# SpeccyPower5v.net
KiCad netlist of a schematic drawn in EAGLE
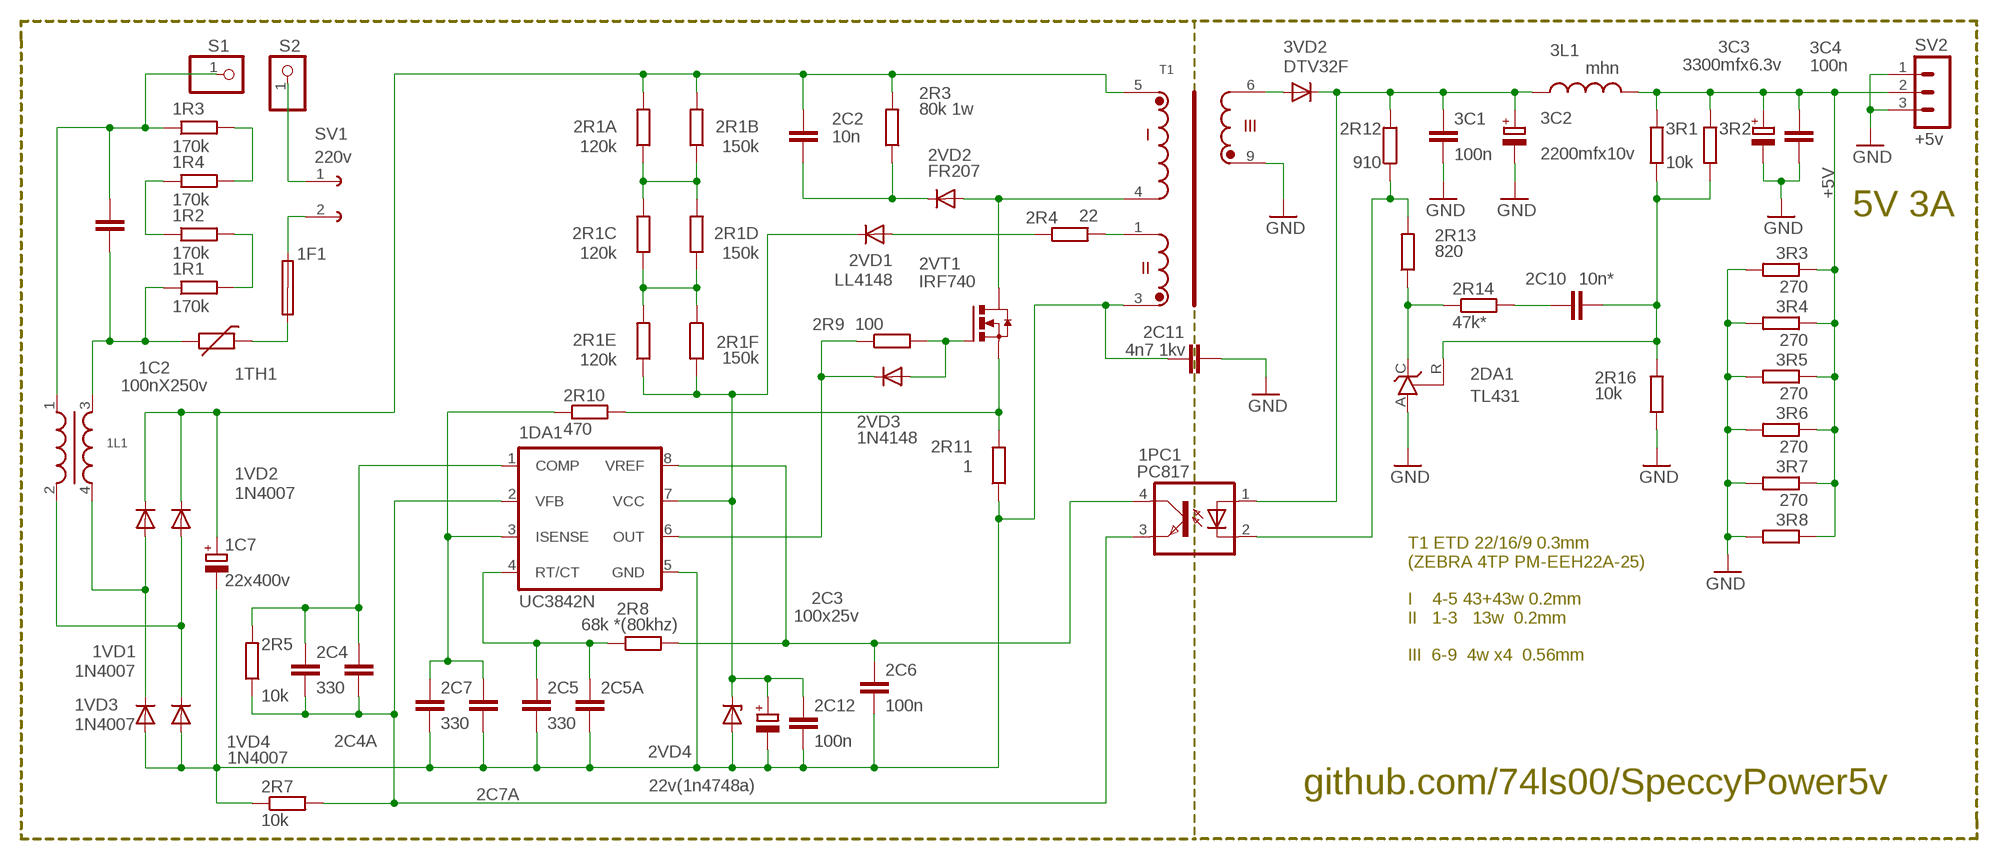
[diagram p0: schematic, sheet 1]

(export (version "E")
  (design (tool "Eeschema 10.0.6"))
  (components
    (comp (ref "1C2")
      (value "100nX250v")
      (footprint "eagle-import:C150-064X183")
      (libsource (lib "eagle-import") (part "C-EU150-064X183"))
    )
    (comp (ref "1C7")
      (value "22x400v")
      (footprint "eagle-import:TT5D11L")
      (libsource (lib "eagle-import") (part "CPOL-EUTT5D11L"))
    )
    (comp (ref "1DA1")
      (value "UC3842N")
      (footprint "eagle-import:DIL08")
      (libsource (lib "eagle-import") (part "UC384N2"))
    )
    (comp (ref "1F1")
      (value "SHK20L")
      (footprint "eagle-import:SHK20L")
      (libsource (lib "eagle-import") (part "SHK20L"))
    )
    (comp (ref "1L1")
      (value "LFLF-10X13")
      (footprint "eagle-import:LF-10X13")
      (libsource (lib "eagle-import") (part "LFLF-10X13"))
    )
    (comp (ref "1PC1")
      (value "PC817")
      (footprint "eagle-import:DIL04")
      (fields (field (name "MPN") "PC817X4J000F"))
      (libsource (lib "eagle-import") (part "PC817"))
    )
    (comp (ref "1R1")
      (value "170k")
      (footprint "eagle-import:R0805")
      (libsource (lib "eagle-import") (part "R-EU_R0805"))
    )
    (comp (ref "1R2")
      (value "170k")
      (footprint "eagle-import:R0805")
      (libsource (lib "eagle-import") (part "R-EU_R0805"))
    )
    (comp (ref "1R3")
      (value "170k")
      (footprint "eagle-import:R0805")
      (libsource (lib "eagle-import") (part "R-EU_R0805"))
    )
    (comp (ref "1R4")
      (value "170k")
      (footprint "eagle-import:R0805")
      (libsource (lib "eagle-import") (part "R-EU_R0805"))
    )
    (comp (ref "1TH1")
      (value "THERMISTOR-7,5")
      (footprint "eagle-import:R-7,5")
      (libsource (lib "eagle-import") (part "THERMISTOR-7,5"))
    )
    (comp (ref "1VD1")
      (value "1N4007")
      (footprint "eagle-import:DO41-10")
      (libsource (lib "eagle-import") (part "1N4004"))
    )
    (comp (ref "1VD2")
      (value "1N4007")
      (footprint "eagle-import:DO41-10")
      (libsource (lib "eagle-import") (part "1N4004"))
    )
    (comp (ref "1VD3")
      (value "1N4007")
      (footprint "eagle-import:DO41-10")
      (libsource (lib "eagle-import") (part "1N4004"))
    )
    (comp (ref "1VD4")
      (value "1N4007")
      (footprint "eagle-import:DO41-10")
      (libsource (lib "eagle-import") (part "1N4004"))
    )
    (comp (ref "2C2")
      (value "10n")
      (footprint "eagle-import:C102-043X133")
      (libsource (lib "eagle-import") (part "rcl_C-EU102-043X133"))
    )
    (comp (ref "2C3")
      (value "100x25v")
      (footprint "eagle-import:E2,5-6")
      (libsource (lib "eagle-import") (part "rcl_CPOL-EUE2.5-6"))
    )
    (comp (ref "2C4")
      (value "330")
      (footprint "eagle-import:C050-025X075")
      (libsource (lib "eagle-import") (part "rcl_C-EU050-025X075"))
    )
    (comp (ref "2C4A")
      (value "C-EUC0805")
      (footprint "eagle-import:C0805")
      (libsource (lib "eagle-import") (part "rcl_C-EUC0805"))
    )
    (comp (ref "2C5")
      (value "330")
      (footprint "eagle-import:C050-025X075")
      (libsource (lib "eagle-import") (part "rcl_C-EU050-025X075"))
    )
    (comp (ref "2C5A")
      (value "C-EUC0805")
      (footprint "eagle-import:C0805")
      (libsource (lib "eagle-import") (part "rcl_C-EUC0805"))
    )
    (comp (ref "2C6")
      (value "100n")
      (footprint "eagle-import:C0805")
      (libsource (lib "eagle-import") (part "rcl_C-EUC0805"))
    )
    (comp (ref "2C7")
      (value "330")
      (footprint "eagle-import:C050-025X075")
      (libsource (lib "eagle-import") (part "rcl_C-EU050-025X075"))
    )
    (comp (ref "2C7A")
      (value "C-EUC0805")
      (footprint "eagle-import:C0805")
      (libsource (lib "eagle-import") (part "rcl_C-EUC0805"))
    )
    (comp (ref "2C10")
      (value "10n*")
      (footprint "eagle-import:C050-025X075")
      (libsource (lib "eagle-import") (part "rcl_C-EU050-025X075"))
    )
    (comp (ref "2C11")
      (value "4n7 1kv")
      (footprint "eagle-import:C075-032X103")
      (libsource (lib "eagle-import") (part "rcl_C-EU075-032X103"))
    )
    (comp (ref "2C12")
      (value "100n")
      (footprint "eagle-import:C0805")
      (libsource (lib "eagle-import") (part "rcl_C-EUC0805"))
    )
    (comp (ref "2DA1")
      (value "TL431")
      (footprint "eagle-import:TO92-CLP")
      (libsource (lib "eagle-import") (part "TL431CLP"))
    )
    (comp (ref "2R1A")
      (value "120k")
      (footprint "eagle-import:M0805")
      (libsource (lib "eagle-import") (part "R-EU_M0805"))
    )
    (comp (ref "2R1B")
      (value "150k")
      (footprint "eagle-import:M0805")
      (libsource (lib "eagle-import") (part "R-EU_M0805"))
    )
    (comp (ref "2R1C")
      (value "120k")
      (footprint "eagle-import:M0805")
      (libsource (lib "eagle-import") (part "R-EU_M0805"))
    )
    (comp (ref "2R1D")
      (value "150k")
      (footprint "eagle-import:M0805")
      (libsource (lib "eagle-import") (part "R-EU_M0805"))
    )
    (comp (ref "2R1E")
      (value "120k")
      (footprint "eagle-import:M0805")
      (libsource (lib "eagle-import") (part "R-EU_M0805"))
    )
    (comp (ref "2R1F")
      (value "150k")
      (footprint "eagle-import:M0805")
      (libsource (lib "eagle-import") (part "R-EU_M0805"))
    )
    (comp (ref "2R3")
      (value "80k 1w")
      (footprint "eagle-import:P0613_15")
      (libsource (lib "eagle-import") (part "R-EU_0613/15"))
    )
    (comp (ref "2R4")
      (value "22")
      (footprint "eagle-import:M0805")
      (libsource (lib "eagle-import") (part "R-EU_M0805"))
    )
    (comp (ref "2R5")
      (value "10k")
      (footprint "eagle-import:0207_10")
      (libsource (lib "eagle-import") (part "R-EU_0207/10"))
    )
    (comp (ref "2R7")
      (value "10k")
      (footprint "eagle-import:0207_10")
      (libsource (lib "eagle-import") (part "R-EU_0207/10"))
    )
    (comp (ref "2R8")
      (value "68k *(80khz)")
      (footprint "eagle-import:R0805")
      (libsource (lib "eagle-import") (part "R-EU_R0805"))
    )
    (comp (ref "2R9")
      (value "100")
      (footprint "eagle-import:0204_7")
      (libsource (lib "eagle-import") (part "R-EU_0204/7"))
    )
    (comp (ref "2R10")
      (value "470")
      (footprint "eagle-import:0207_10")
      (libsource (lib "eagle-import") (part "R-EU_0207/10"))
    )
    (comp (ref "2R11")
      (value "1")
      (footprint "eagle-import:0411_15")
      (libsource (lib "eagle-import") (part "R-EU_0411/15"))
    )
    (comp (ref "2R12")
      (value "910")
      (footprint "eagle-import:R0805")
      (libsource (lib "eagle-import") (part "R-EU_R0805"))
    )
    (comp (ref "2R13")
      (value "820")
      (footprint "eagle-import:0204_7")
      (libsource (lib "eagle-import") (part "R-EU_0204/7"))
    )
    (comp (ref "2R14")
      (value "47k*")
      (footprint "eagle-import:R0805")
      (libsource (lib "eagle-import") (part "R-EU_R0805"))
    )
    (comp (ref "2R16")
      (value "10k")
      (footprint "eagle-import:R0805")
      (libsource (lib "eagle-import") (part "R-EU_R0805"))
    )
    (comp (ref "2VD1")
      (value "LL4148")
      (footprint "eagle-import:SOD80C")
      (libsource (lib "eagle-import") (part "DIODE-SOD80C"))
    )
    (comp (ref "2VD2")
      (value "FR207")
      (footprint "eagle-import:DO35-10")
      (libsource (lib "eagle-import") (part "1N4148DO35-10"))
    )
    (comp (ref "2VD3")
      (value "1N4148")
      (footprint "eagle-import:DO35-7")
      (libsource (lib "eagle-import") (part "1N4148DO35-7"))
    )
    (comp (ref "2VD4")
      (value "22v(1n4748a)")
      (footprint "eagle-import:DO35Z10")
      (libsource (lib "eagle-import") (part "ZENER-DIODEDO35Z10"))
    )
    (comp (ref "2VT1")
      (value "IRF740")
      (footprint "eagle-import:TO262-V")
      (libsource (lib "eagle-import") (part "IRF3704L-V"))
    )
    (comp (ref "3C1")
      (value "100n")
      (footprint "eagle-import:C0805")
      (libsource (lib "eagle-import") (part "rcl_C-EUC0805"))
    )
    (comp (ref "3C2")
      (value "2200mfx10v")
      (footprint "eagle-import:TT2D7L")
      (libsource (lib "eagle-import") (part "CPOL-EUTT2D7L"))
    )
    (comp (ref "3C3")
      (value "3300mfx6.3v")
      (footprint "eagle-import:TT2D7L-2")
      (libsource (lib "eagle-import") (part "CPOL-EUTT2D7L-2"))
    )
    (comp (ref "3C4")
      (value "100n")
      (footprint "eagle-import:C0805")
      (libsource (lib "eagle-import") (part "rcl_C-EUC0805"))
    )
    (comp (ref "3L1")
      (value "mhn")
      (footprint "eagle-import:LAL02")
      (libsource (lib "eagle-import") (part "L-USLAL02"))
    )
    (comp (ref "3R1")
      (value "10k")
      (footprint "eagle-import:R0805")
      (libsource (lib "eagle-import") (part "R-EU_R0805"))
    )
    (comp (ref "3R2")
      (value "R-EU_R0805")
      (footprint "eagle-import:R0805")
      (libsource (lib "eagle-import") (part "R-EU_R0805"))
    )
    (comp (ref "3R3")
      (value "270")
      (footprint "eagle-import:R0805")
      (libsource (lib "eagle-import") (part "R-EU_R0805"))
    )
    (comp (ref "3R4")
      (value "270")
      (footprint "eagle-import:R0805")
      (libsource (lib "eagle-import") (part "R-EU_R0805"))
    )
    (comp (ref "3R5")
      (value "270")
      (footprint "eagle-import:R0805")
      (libsource (lib "eagle-import") (part "R-EU_R0805"))
    )
    (comp (ref "3R6")
      (value "270")
      (footprint "eagle-import:R0805")
      (libsource (lib "eagle-import") (part "R-EU_R0805"))
    )
    (comp (ref "3R7")
      (value "270")
      (footprint "eagle-import:R0805")
      (libsource (lib "eagle-import") (part "R-EU_R0805"))
    )
    (comp (ref "3R8")
      (value "R-EU_R0805")
      (footprint "eagle-import:R0805")
      (libsource (lib "eagle-import") (part "R-EU_R0805"))
    )
    (comp (ref "3VD2")
      (value "DTV32F")
      (footprint "eagle-import:DO220S")
      (libsource (lib "eagle-import") (part "DIODE-DO220S"))
    )
    (comp (ref "S1")
      (value "PINHD-1X1")
      (footprint "eagle-import:1X01")
      (libsource (lib "eagle-import") (part "PINHD-1X1"))
    )
    (comp (ref "S2")
      (value "PINHD-1X1")
      (footprint "eagle-import:1X01")
      (libsource (lib "eagle-import") (part "PINHD-1X1"))
    )
    (comp (ref "SV1")
      (value "220v")
      (footprint "eagle-import:IEC320-C8")
      (libsource (lib "eagle-import") (part "IEC320-C8"))
    )
    (comp (ref "SV2")
      (value "+5v")
      (footprint "eagle-import:MA03-1")
      (libsource (lib "eagle-import") (part "MA03-1"))
    )
    (comp (ref "T1")
      (value "TRANS_ER29")
      (footprint "eagle-import:ER29")
      (libsource (lib "eagle-import") (part "TRANS_ER29"))
    )
  )
  (nets
    (net (code "1") (name "/+5V") (class "Default")
      (node (ref "3C3") (pin "+") (pinfunction "+_+") (pintype "passive"))
      (node (ref "3C4") (pin "1") (pinfunction "1_1") (pintype "passive"))
      (node (ref "3L1") (pin "2") (pinfunction "2_2") (pintype "passive"))
      (node (ref "3R1") (pin "2") (pinfunction "2_2") (pintype "passive"))
      (node (ref "3R2") (pin "2") (pinfunction "2_2") (pintype "passive"))
      (node (ref "3R3") (pin "1") (pinfunction "1_1") (pintype "passive"))
      (node (ref "3R4") (pin "1") (pinfunction "1_1") (pintype "passive"))
      (node (ref "3R5") (pin "1") (pinfunction "1_1") (pintype "passive"))
      (node (ref "3R6") (pin "1") (pinfunction "1_1") (pintype "passive"))
      (node (ref "3R7") (pin "1") (pinfunction "1_1") (pintype "passive"))
      (node (ref "3R8") (pin "1") (pinfunction "1_1") (pintype "passive"))
      (node (ref "SV2") (pin "2") (pinfunction "2_2") (pintype "passive"))
    )
    (net (code "2") (name "GND") (class "Default")
      (node (ref "2C11") (pin "2") (pinfunction "2_2") (pintype "passive"))
      (node (ref "2DA1") (pin "A") (pinfunction "A_A") (pintype "passive"))
      (node (ref "2R16") (pin "1") (pinfunction "1_1") (pintype "passive"))
      (node (ref "3C1") (pin "2") (pinfunction "2_2") (pintype "passive"))
      (node (ref "3C2") (pin "-") (pinfunction "-_-") (pintype "passive"))
      (node (ref "3C3") (pin "-") (pinfunction "-_-") (pintype "passive"))
      (node (ref "3C4") (pin "2") (pinfunction "2_2") (pintype "passive"))
      (node (ref "3R3") (pin "2") (pinfunction "2_2") (pintype "passive"))
      (node (ref "3R4") (pin "2") (pinfunction "2_2") (pintype "passive"))
      (node (ref "3R5") (pin "2") (pinfunction "2_2") (pintype "passive"))
      (node (ref "3R6") (pin "2") (pinfunction "2_2") (pintype "passive"))
      (node (ref "3R7") (pin "2") (pinfunction "2_2") (pintype "passive"))
      (node (ref "3R8") (pin "2") (pinfunction "2_2") (pintype "passive"))
      (node (ref "SV2") (pin "1") (pinfunction "1_1") (pintype "passive"))
      (node (ref "SV2") (pin "3") (pinfunction "3_3") (pintype "passive"))
      (node (ref "T1") (pin "9") (pinfunction "5V2_9") (pintype "bidirectional"))
    )
    (net (code "3") (name "Net-(1C2-Pad1)") (class "Default")
      (node (ref "1C2") (pin "1") (pinfunction "1_1") (pintype "passive"))
      (node (ref "1L1") (pin "3") (pinfunction "3_3") (pintype "bidirectional"))
      (node (ref "1R1") (pin "1") (pinfunction "1_1") (pintype "passive"))
      (node (ref "1TH1") (pin "2") (pinfunction "2_2") (pintype "passive"))
    )
    (net (code "4") (name "Net-(1C2-Pad2)") (class "Default")
      (node (ref "1C2") (pin "2") (pinfunction "2_2") (pintype "passive"))
      (node (ref "1L1") (pin "1") (pinfunction "1_1") (pintype "bidirectional"))
      (node (ref "1R3") (pin "1") (pinfunction "1_1") (pintype "passive"))
      (node (ref "S1") (pin "1") (pinfunction "1_1") (pintype "passive"))
    )
    (net (code "5") (name "Net-(1DA1-COMP)") (class "Default")
      (node (ref "1DA1") (pin "1") (pinfunction "COMP_1") (pintype "passive"))
      (node (ref "2C4") (pin "1") (pinfunction "1_1") (pintype "passive"))
      (node (ref "2C4A") (pin "1") (pinfunction "1_1") (pintype "passive"))
      (node (ref "2R5") (pin "2") (pinfunction "2_2") (pintype "passive"))
    )
    (net (code "6") (name "Net-(1DA1-GND)") (class "Default")
      (node (ref "1C7") (pin "-") (pinfunction "-_-") (pintype "passive"))
      (node (ref "1DA1") (pin "5") (pinfunction "GND_5") (pintype "power_in"))
      (node (ref "1VD3") (pin "A") (pinfunction "A_A") (pintype "passive"))
      (node (ref "1VD4") (pin "A") (pinfunction "A_A") (pintype "passive"))
      (node (ref "2C11") (pin "1") (pinfunction "1_1") (pintype "passive"))
      (node (ref "2C12") (pin "2") (pinfunction "2_2") (pintype "passive"))
      (node (ref "2C3") (pin "-") (pinfunction "-_-") (pintype "passive"))
      (node (ref "2C5") (pin "2") (pinfunction "2_2") (pintype "passive"))
      (node (ref "2C5A") (pin "2") (pinfunction "2_2") (pintype "passive"))
      (node (ref "2C6") (pin "2") (pinfunction "2_2") (pintype "passive"))
      (node (ref "2C7") (pin "2") (pinfunction "2_2") (pintype "passive"))
      (node (ref "2C7A") (pin "2") (pinfunction "2_2") (pintype "passive"))
      (node (ref "2R11") (pin "1") (pinfunction "1_1") (pintype "passive"))
      (node (ref "2R7") (pin "1") (pinfunction "1_1") (pintype "passive"))
      (node (ref "2VD4") (pin "A") (pinfunction "A_A") (pintype "passive"))
      (node (ref "T1") (pin "3") (pinfunction "OP2_3") (pintype "bidirectional"))
    )
    (net (code "7") (name "Net-(1DA1-ISENSE)") (class "Default")
      (node (ref "1DA1") (pin "3") (pinfunction "ISENSE_3") (pintype "input"))
      (node (ref "2C7") (pin "1") (pinfunction "1_1") (pintype "passive"))
      (node (ref "2C7A") (pin "1") (pinfunction "1_1") (pintype "passive"))
      (node (ref "2R10") (pin "1") (pinfunction "1_1") (pintype "passive"))
    )
    (net (code "8") (name "Net-(1DA1-OUT)") (class "Default")
      (node (ref "1DA1") (pin "6") (pinfunction "OUT_6") (pintype "output"))
      (node (ref "2R9") (pin "1") (pinfunction "1_1") (pintype "passive"))
      (node (ref "2VD3") (pin "C") (pinfunction "C_C") (pintype "passive"))
    )
    (net (code "9") (name "Net-(1DA1-RT{slash}CT)") (class "Default")
      (node (ref "1DA1") (pin "4") (pinfunction "RT/CT_4") (pintype "passive"))
      (node (ref "2C5") (pin "1") (pinfunction "1_1") (pintype "passive"))
      (node (ref "2C5A") (pin "1") (pinfunction "1_1") (pintype "passive"))
      (node (ref "2R8") (pin "1") (pinfunction "1_1") (pintype "passive"))
    )
    (net (code "10") (name "Net-(1DA1-VCC)") (class "Default")
      (node (ref "1DA1") (pin "7") (pinfunction "VCC_7") (pintype "power_in"))
      (node (ref "2C12") (pin "1") (pinfunction "1_1") (pintype "passive"))
      (node (ref "2C3") (pin "+") (pinfunction "+_+") (pintype "passive"))
      (node (ref "2R1E") (pin "1") (pinfunction "1_1") (pintype "passive"))
      (node (ref "2R1F") (pin "2") (pinfunction "2_2") (pintype "passive"))
      (node (ref "2VD1") (pin "C") (pinfunction "C_C") (pintype "passive"))
      (node (ref "2VD4") (pin "C") (pinfunction "C_C") (pintype "passive"))
    )
    (net (code "11") (name "Net-(1DA1-VFB)") (class "Default")
      (node (ref "1DA1") (pin "2") (pinfunction "VFB_2") (pintype "input"))
      (node (ref "1PC1") (pin "3") (pinfunction "EMIT_3") (pintype "passive"))
      (node (ref "2C4") (pin "2") (pinfunction "2_2") (pintype "passive"))
      (node (ref "2C4A") (pin "2") (pinfunction "2_2") (pintype "passive"))
      (node (ref "2R5") (pin "1") (pinfunction "1_1") (pintype "passive"))
      (node (ref "2R7") (pin "2") (pinfunction "2_2") (pintype "passive"))
    )
    (net (code "12") (name "Net-(1DA1-VREF)") (class "Default")
      (node (ref "1DA1") (pin "8") (pinfunction "VREF_8") (pintype "passive"))
      (node (ref "1PC1") (pin "4") (pinfunction "COL_4") (pintype "passive"))
      (node (ref "2C6") (pin "1") (pinfunction "1_1") (pintype "passive"))
      (node (ref "2R8") (pin "2") (pinfunction "2_2") (pintype "passive"))
    )
    (net (code "13") (name "Net-(1F1-Pad1A)") (class "Default")
      (node (ref "1F1") (pin "1A") (pinfunction "1A_1A") (pintype "passive"))
      (node (ref "SV1") (pin "2") (pinfunction "2_2") (pintype "passive"))
    )
    (net (code "14") (name "Net-(1F1-Pad2A)") (class "Default")
      (node (ref "1F1") (pin "2A") (pinfunction "2A_2A") (pintype "passive"))
      (node (ref "1TH1") (pin "1") (pinfunction "1_1") (pintype "passive"))
    )
    (net (code "15") (name "Net-(1L1-Pad2)") (class "Default")
      (node (ref "1L1") (pin "2") (pinfunction "2_2") (pintype "bidirectional"))
      (node (ref "1VD2") (pin "A") (pinfunction "A_A") (pintype "passive"))
      (node (ref "1VD4") (pin "C") (pinfunction "C_C") (pintype "passive"))
    )
    (net (code "16") (name "Net-(1L1-Pad4)") (class "Default")
      (node (ref "1L1") (pin "4") (pinfunction "4_4") (pintype "bidirectional"))
      (node (ref "1VD1") (pin "A") (pinfunction "A_A") (pintype "passive"))
      (node (ref "1VD3") (pin "C") (pinfunction "C_C") (pintype "passive"))
    )
    (net (code "17") (name "Net-(1PC1-A)") (class "Default")
      (node (ref "1PC1") (pin "1") (pinfunction "A_1") (pintype "passive"))
      (node (ref "2R12") (pin "2") (pinfunction "2_2") (pintype "passive"))
      (node (ref "3C1") (pin "1") (pinfunction "1_1") (pintype "passive"))
      (node (ref "3C2") (pin "+") (pinfunction "+_+") (pintype "passive"))
      (node (ref "3L1") (pin "1") (pinfunction "1_1") (pintype "passive"))
      (node (ref "3VD2") (pin "C") (pinfunction "C_C") (pintype "passive"))
    )
    (net (code "18") (name "Net-(1PC1-C)") (class "Default")
      (node (ref "1PC1") (pin "2") (pinfunction "C_2") (pintype "passive"))
      (node (ref "2R12") (pin "1") (pinfunction "1_1") (pintype "passive"))
      (node (ref "2R13") (pin "2") (pinfunction "2_2") (pintype "passive"))
    )
    (net (code "19") (name "Net-(1R1-Pad2)") (class "Default")
      (node (ref "1R1") (pin "2") (pinfunction "2_2") (pintype "passive"))
      (node (ref "1R2") (pin "2") (pinfunction "2_2") (pintype "passive"))
    )
    (net (code "20") (name "Net-(1R2-Pad1)") (class "Default")
      (node (ref "1R2") (pin "1") (pinfunction "1_1") (pintype "passive"))
      (node (ref "1R4") (pin "1") (pinfunction "1_1") (pintype "passive"))
    )
    (net (code "21") (name "Net-(1R3-Pad2)") (class "Default")
      (node (ref "1R3") (pin "2") (pinfunction "2_2") (pintype "passive"))
      (node (ref "1R4") (pin "2") (pinfunction "2_2") (pintype "passive"))
    )
    (net (code "22") (name "Net-(2C2-Pad2)") (class "Default")
      (node (ref "2C2") (pin "2") (pinfunction "2_2") (pintype "passive"))
      (node (ref "2R3") (pin "1") (pinfunction "1_1") (pintype "passive"))
      (node (ref "2VD2") (pin "C") (pinfunction "C_C") (pintype "passive"))
    )
    (net (code "23") (name "Net-(2C10-Pad1)") (class "Default")
      (node (ref "2C10") (pin "1") (pinfunction "1_1") (pintype "passive"))
      (node (ref "2DA1") (pin "R") (pinfunction "R_R") (pintype "passive"))
      (node (ref "2R16") (pin "2") (pinfunction "2_2") (pintype "passive"))
      (node (ref "3R1") (pin "1") (pinfunction "1_1") (pintype "passive"))
      (node (ref "3R2") (pin "1") (pinfunction "1_1") (pintype "passive"))
    )
    (net (code "24") (name "Net-(2C10-Pad2)") (class "Default")
      (node (ref "2C10") (pin "2") (pinfunction "2_2") (pintype "passive"))
      (node (ref "2R14") (pin "2") (pinfunction "2_2") (pintype "passive"))
    )
    (net (code "25") (name "Net-(2DA1-PadC)") (class "Default")
      (node (ref "2DA1") (pin "C") (pinfunction "C_C") (pintype "passive"))
      (node (ref "2R13") (pin "1") (pinfunction "1_1") (pintype "passive"))
      (node (ref "2R14") (pin "1") (pinfunction "1_1") (pintype "passive"))
    )
    (net (code "26") (name "Net-(2R1A-Pad1)") (class "Default")
      (node (ref "2R1A") (pin "1") (pinfunction "1_1") (pintype "passive"))
      (node (ref "2R1B") (pin "1") (pinfunction "1_1") (pintype "passive"))
      (node (ref "2R1C") (pin "2") (pinfunction "2_2") (pintype "passive"))
      (node (ref "2R1D") (pin "2") (pinfunction "2_2") (pintype "passive"))
    )
    (net (code "27") (name "Net-(2R1C-Pad1)") (class "Default")
      (node (ref "2R1C") (pin "1") (pinfunction "1_1") (pintype "passive"))
      (node (ref "2R1D") (pin "1") (pinfunction "1_1") (pintype "passive"))
      (node (ref "2R1E") (pin "2") (pinfunction "2_2") (pintype "passive"))
      (node (ref "2R1F") (pin "1") (pinfunction "1_1") (pintype "passive"))
    )
    (net (code "28") (name "Net-(2R4-Pad1)") (class "Default")
      (node (ref "2R4") (pin "1") (pinfunction "1_1") (pintype "passive"))
      (node (ref "2VD1") (pin "A") (pinfunction "A_A") (pintype "passive"))
    )
    (net (code "29") (name "Net-(2VT1-D)") (class "Default")
      (node (ref "2VD2") (pin "A") (pinfunction "A_A") (pintype "passive"))
      (node (ref "2VT1") (pin "2") (pinfunction "D_2") (pintype "passive"))
      (node (ref "T1") (pin "4") (pinfunction "IN1_4") (pintype "bidirectional"))
    )
    (net (code "30") (name "Net-(2VT1-G)") (class "Default")
      (node (ref "2R9") (pin "2") (pinfunction "2_2") (pintype "passive"))
      (node (ref "2VD3") (pin "A") (pinfunction "A_A") (pintype "passive"))
      (node (ref "2VT1") (pin "1") (pinfunction "G_1") (pintype "passive"))
    )
    (net (code "31") (name "Net-(2VT1-S)") (class "Default")
      (node (ref "2R10") (pin "2") (pinfunction "2_2") (pintype "passive"))
      (node (ref "2R11") (pin "2") (pinfunction "2_2") (pintype "passive"))
      (node (ref "2VT1") (pin "3") (pinfunction "S_3") (pintype "passive"))
    )
    (net (code "32") (name "Net-(S2-Pad1)") (class "Default")
      (node (ref "S2") (pin "1") (pinfunction "1_1") (pintype "passive"))
      (node (ref "SV1") (pin "1") (pinfunction "1_1") (pintype "passive"))
    )
    (net (code "33") (name "Net-(T1-5V1)") (class "Default")
      (node (ref "3VD2") (pin "A") (pinfunction "A_A") (pintype "passive"))
      (node (ref "T1") (pin "6") (pinfunction "5V1_6") (pintype "bidirectional"))
    )
    (net (code "34") (name "Net-(T1-IN2)") (class "Default")
      (node (ref "1C7") (pin "+") (pinfunction "+_+") (pintype "passive"))
      (node (ref "1VD1") (pin "C") (pinfunction "C_C") (pintype "passive"))
      (node (ref "1VD2") (pin "C") (pinfunction "C_C") (pintype "passive"))
      (node (ref "2C2") (pin "1") (pinfunction "1_1") (pintype "passive"))
      (node (ref "2R1A") (pin "2") (pinfunction "2_2") (pintype "passive"))
      (node (ref "2R1B") (pin "2") (pinfunction "2_2") (pintype "passive"))
      (node (ref "2R3") (pin "2") (pinfunction "2_2") (pintype "passive"))
      (node (ref "T1") (pin "5") (pinfunction "IN2_5") (pintype "bidirectional"))
    )
    (net (code "35") (name "Net-(T1-OP1)") (class "Default")
      (node (ref "2R4") (pin "2") (pinfunction "2_2") (pintype "passive"))
      (node (ref "T1") (pin "1") (pinfunction "OP1_1") (pintype "bidirectional"))
    )
    (net (code "36") (name "unconnected-(1F1-Pad1B)") (class "Default")
      (node (ref "1F1") (pin "1B") (pinfunction "1B_1B") (pintype "passive"))
    )
    (net (code "37") (name "unconnected-(1F1-Pad2B)") (class "Default")
      (node (ref "1F1") (pin "2B") (pinfunction "2B_2B") (pintype "passive"))
    )
  )
)
